# mb.net
KiCad netlist of a schematic drawn in Altium Designer
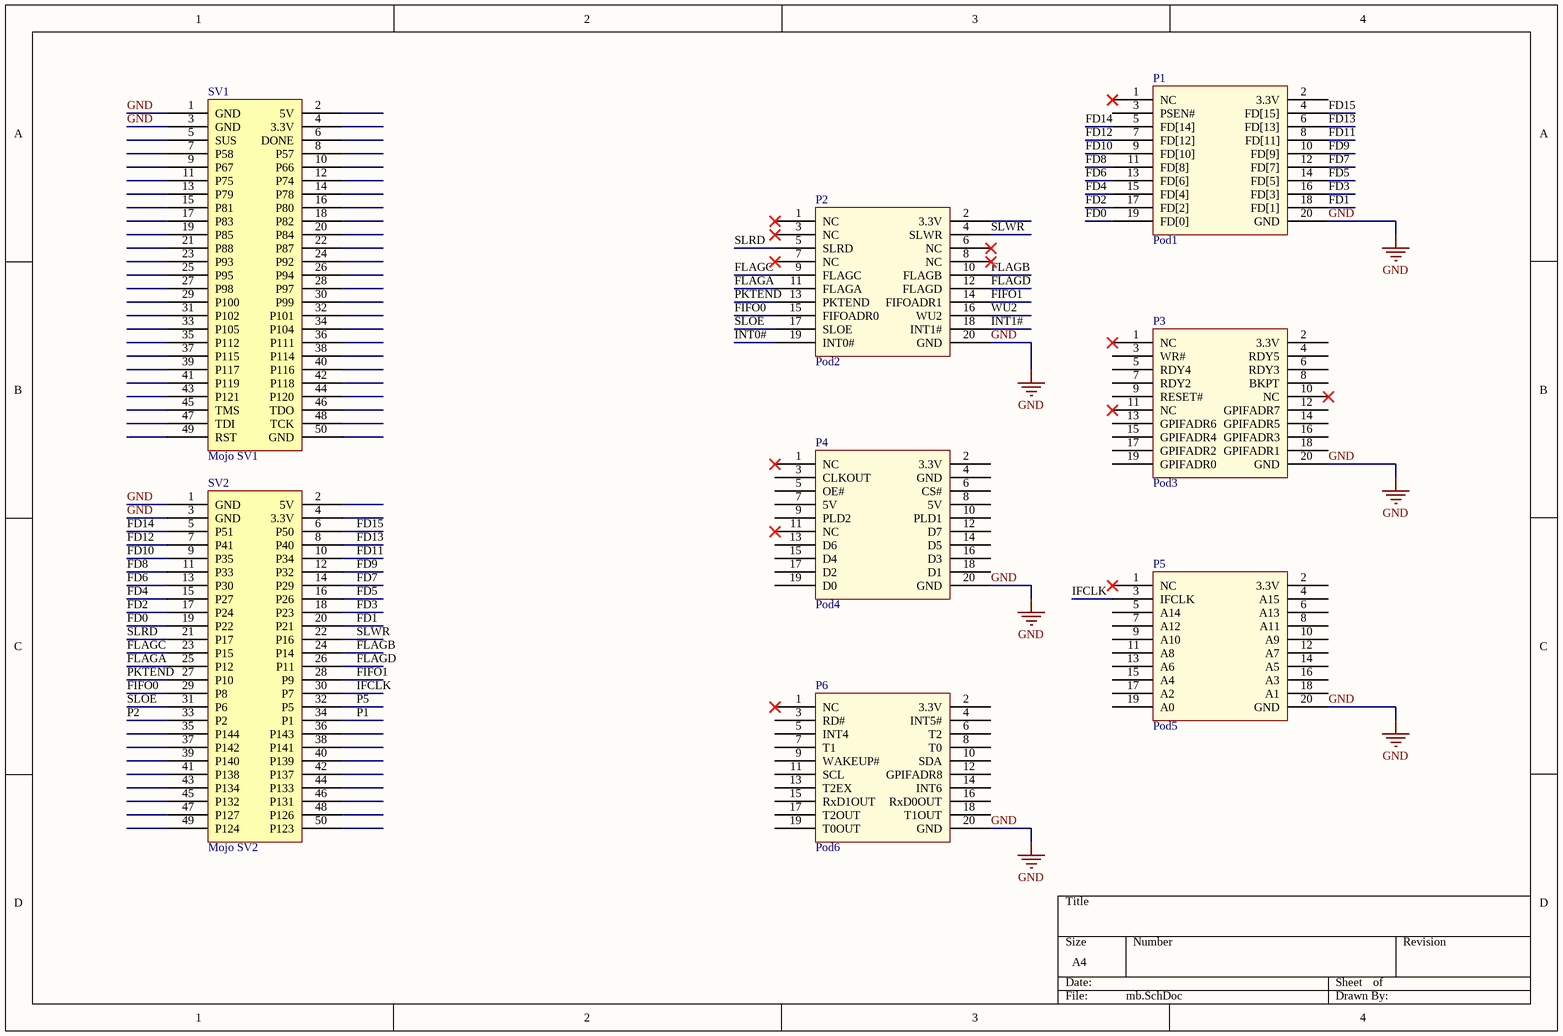
[diagram p0: mb.SchDoc]

(export (version "E")
  (design (tool "Eeschema 10.0.6"))
  (components
    (comp (ref "P1") (value "Pod1") (footprint "Pin Header 20x2") (libsource (lib "port1") (part "P*")))
    (comp (ref "P2") (value "Pod2") (footprint "Pin Header 20x2") (libsource (lib "port2") (part "Pod2")))
    (comp (ref "P3") (value "Pod3") (footprint "Pin Header 20x2") (libsource (lib "port3") (part "Pod3")))
    (comp (ref "P4") (value "Pod4") (footprint "Pin Header 20x2") (libsource (lib "port4") (part "Pod4")))
    (comp (ref "P5") (value "Pod5") (footprint "Pin Header 20x2") (libsource (lib "port5") (part "Pod5")))
    (comp (ref "P6") (value "Pod6") (footprint "Pin Header 20x2") (libsource (lib "port6") (part "Pod6")))
    (comp (ref "SV1") (value "Mojo SV1") (footprint "PH25X2") (libsource (lib "mojosv1") (part "SV1")))
    (comp (ref "SV2") (value "Mojo SV2") (footprint "PH25X2") (libsource (lib "mojosv2") (part "SV2")))
  )
  (nets
    (net (code "1") (name "/FD0") (class "Default")
      (node (ref "P1") (pin "19") (pinfunction "FD[0]_19") (pintype "passive"))
      (node (ref "SV2") (pin "19") (pinfunction "P22_19") (pintype "passive"))
    )
    (net (code "2") (name "/FD1") (class "Default")
      (node (ref "P1") (pin "18") (pinfunction "FD[1]_18") (pintype "passive"))
      (node (ref "SV2") (pin "20") (pinfunction "P21_20") (pintype "passive"))
    )
    (net (code "3") (name "/FD2") (class "Default")
      (node (ref "P1") (pin "17") (pinfunction "FD[2]_17") (pintype "passive"))
      (node (ref "SV2") (pin "17") (pinfunction "P24_17") (pintype "passive"))
    )
    (net (code "4") (name "/FD3") (class "Default")
      (node (ref "P1") (pin "16") (pinfunction "FD[3]_16") (pintype "passive"))
      (node (ref "SV2") (pin "18") (pinfunction "P23_18") (pintype "passive"))
    )
    (net (code "5") (name "/FD4") (class "Default")
      (node (ref "P1") (pin "15") (pinfunction "FD[4]_15") (pintype "passive"))
      (node (ref "SV2") (pin "15") (pinfunction "P27_15") (pintype "passive"))
    )
    (net (code "6") (name "/FD5") (class "Default")
      (node (ref "P1") (pin "14") (pinfunction "FD[5]_14") (pintype "passive"))
      (node (ref "SV2") (pin "16") (pinfunction "P26_16") (pintype "passive"))
    )
    (net (code "7") (name "/FD6") (class "Default")
      (node (ref "P1") (pin "13") (pinfunction "FD[6]_13") (pintype "passive"))
      (node (ref "SV2") (pin "13") (pinfunction "P30_13") (pintype "passive"))
    )
    (net (code "8") (name "/FD7") (class "Default")
      (node (ref "P1") (pin "12") (pinfunction "FD[7]_12") (pintype "passive"))
      (node (ref "SV2") (pin "14") (pinfunction "P29_14") (pintype "passive"))
    )
    (net (code "9") (name "/FD8") (class "Default")
      (node (ref "P1") (pin "11") (pinfunction "FD[8]_11") (pintype "passive"))
      (node (ref "SV2") (pin "11") (pinfunction "P33_11") (pintype "passive"))
    )
    (net (code "10") (name "/FD9") (class "Default")
      (node (ref "P1") (pin "10") (pinfunction "FD[9]_10") (pintype "passive"))
      (node (ref "SV2") (pin "12") (pinfunction "P32_12") (pintype "passive"))
    )
    (net (code "11") (name "/FD10") (class "Default")
      (node (ref "P1") (pin "9") (pinfunction "FD[10]_9") (pintype "passive"))
      (node (ref "SV2") (pin "9") (pinfunction "P35_9") (pintype "passive"))
    )
    (net (code "12") (name "/FD11") (class "Default")
      (node (ref "P1") (pin "8") (pinfunction "FD[11]_8") (pintype "passive"))
      (node (ref "SV2") (pin "10") (pinfunction "P34_10") (pintype "passive"))
    )
    (net (code "13") (name "/FD12") (class "Default")
      (node (ref "P1") (pin "7") (pinfunction "FD[12]_7") (pintype "passive"))
      (node (ref "SV2") (pin "7") (pinfunction "P41_7") (pintype "passive"))
    )
    (net (code "14") (name "/FD13") (class "Default")
      (node (ref "P1") (pin "6") (pinfunction "FD[13]_6") (pintype "passive"))
      (node (ref "SV2") (pin "8") (pinfunction "P40_8") (pintype "passive"))
    )
    (net (code "15") (name "/FD14") (class "Default")
      (node (ref "P1") (pin "5") (pinfunction "FD[14]_5") (pintype "passive"))
      (node (ref "SV2") (pin "5") (pinfunction "P51_5") (pintype "passive"))
    )
    (net (code "16") (name "/FD15") (class "Default")
      (node (ref "P1") (pin "4") (pinfunction "FD[15]_4") (pintype "passive"))
      (node (ref "SV2") (pin "6") (pinfunction "P50_6") (pintype "passive"))
    )
    (net (code "17") (name "/FIFO0") (class "Default")
      (node (ref "P2") (pin "15") (pinfunction "FIFOADR0_15") (pintype "passive"))
      (node (ref "SV2") (pin "29") (pinfunction "P8_29") (pintype "passive"))
    )
    (net (code "18") (name "/FIFO1") (class "Default")
      (node (ref "P2") (pin "14") (pinfunction "FIFOADR1_14") (pintype "passive"))
      (node (ref "SV2") (pin "28") (pinfunction "P9_28") (pintype "passive"))
    )
    (net (code "19") (name "/FLAGA") (class "Default")
      (node (ref "P2") (pin "11") (pinfunction "FLAGA_11") (pintype "passive"))
      (node (ref "SV2") (pin "25") (pinfunction "P12_25") (pintype "passive"))
    )
    (net (code "20") (name "/FLAGB") (class "Default")
      (node (ref "P2") (pin "10") (pinfunction "FLAGB_10") (pintype "passive"))
      (node (ref "SV2") (pin "24") (pinfunction "P14_24") (pintype "passive"))
    )
    (net (code "21") (name "/FLAGC") (class "Default")
      (node (ref "P2") (pin "9") (pinfunction "FLAGC_9") (pintype "passive"))
      (node (ref "SV2") (pin "23") (pinfunction "P15_23") (pintype "passive"))
    )
    (net (code "22") (name "/FLAGD") (class "Default")
      (node (ref "P2") (pin "12") (pinfunction "FLAGD_12") (pintype "passive"))
      (node (ref "SV2") (pin "26") (pinfunction "P11_26") (pintype "passive"))
    )
    (net (code "23") (name "/IFCLK") (class "Default")
      (node (ref "P5") (pin "3") (pinfunction "IFCLK_3") (pintype "passive"))
      (node (ref "SV2") (pin "30") (pinfunction "P7_30") (pintype "passive"))
    )
    (net (code "24") (name "/INT0#") (class "Default")
      (node (ref "P2") (pin "19") (pinfunction "INT0#_19") (pintype "passive"))
    )
    (net (code "25") (name "/INT1#") (class "Default")
      (node (ref "P2") (pin "18") (pinfunction "INT1#_18") (pintype "passive"))
    )
    (net (code "26") (name "/P1") (class "Default")
      (node (ref "SV2") (pin "34") (pinfunction "P1_34") (pintype "passive"))
    )
    (net (code "27") (name "/P2") (class "Default")
      (node (ref "SV2") (pin "33") (pinfunction "P2_33") (pintype "passive"))
    )
    (net (code "28") (name "/P5") (class "Default")
      (node (ref "SV2") (pin "32") (pinfunction "P5_32") (pintype "passive"))
    )
    (net (code "29") (name "/PKTEND") (class "Default")
      (node (ref "P2") (pin "13") (pinfunction "PKTEND_13") (pintype "passive"))
      (node (ref "SV2") (pin "27") (pinfunction "P10_27") (pintype "passive"))
    )
    (net (code "30") (name "/SLOE") (class "Default")
      (node (ref "P2") (pin "17") (pinfunction "SLOE_17") (pintype "passive"))
      (node (ref "SV2") (pin "31") (pinfunction "P6_31") (pintype "passive"))
    )
    (net (code "31") (name "/SLRD") (class "Default")
      (node (ref "P2") (pin "5") (pinfunction "SLRD_5") (pintype "passive"))
      (node (ref "SV2") (pin "21") (pinfunction "P17_21") (pintype "passive"))
    )
    (net (code "32") (name "/SLWR") (class "Default")
      (node (ref "P2") (pin "4") (pinfunction "SLWR_4") (pintype "passive"))
      (node (ref "SV2") (pin "22") (pinfunction "P16_22") (pintype "passive"))
    )
    (net (code "33") (name "/WU2") (class "Default")
      (node (ref "P2") (pin "16") (pinfunction "WU2_16") (pintype "passive"))
    )
    (net (code "34") (name "GND") (class "Default")
      (node (ref "P1") (pin "20") (pinfunction "GND_20") (pintype "passive"))
      (node (ref "P2") (pin "20") (pinfunction "GND_20") (pintype "passive"))
      (node (ref "P3") (pin "20") (pinfunction "GND_20") (pintype "passive"))
      (node (ref "P4") (pin "20") (pinfunction "GND_20") (pintype "passive"))
      (node (ref "P5") (pin "20") (pinfunction "GND_20") (pintype "passive"))
      (node (ref "P6") (pin "20") (pinfunction "GND_20") (pintype "passive"))
      (node (ref "SV1") (pin "1") (pinfunction "GND_1") (pintype "passive"))
      (node (ref "SV1") (pin "3") (pinfunction "GND_3") (pintype "passive"))
      (node (ref "SV2") (pin "1") (pinfunction "GND_1") (pintype "passive"))
      (node (ref "SV2") (pin "3") (pinfunction "GND_3") (pintype "passive"))
    )
    (net (code "35") (name "unconnected-(P1-3.3V-Pad2)") (class "Default")
      (node (ref "P1") (pin "2") (pinfunction "3.3V_2") (pintype "passive"))
    )
    (net (code "36") (name "unconnected-(P1-NC-Pad1)") (class "Default")
      (node (ref "P1") (pin "1") (pinfunction "NC_1") (pintype "passive+no_connect"))
    )
    (net (code "37") (name "unconnected-(P1-PSEN#-Pad3)") (class "Default")
      (node (ref "P1") (pin "3") (pinfunction "PSEN#_3") (pintype "passive"))
    )
    (net (code "38") (name "unconnected-(P2-3.3V-Pad2)") (class "Default")
      (node (ref "P2") (pin "2") (pinfunction "3.3V_2") (pintype "passive"))
    )
    (net (code "39") (name "unconnected-(P2-NC-Pad1)") (class "Default")
      (node (ref "P2") (pin "1") (pinfunction "NC_1") (pintype "passive+no_connect"))
    )
    (net (code "40") (name "unconnected-(P2-NC-Pad3)") (class "Default")
      (node (ref "P2") (pin "3") (pinfunction "NC_3") (pintype "passive+no_connect"))
    )
    (net (code "41") (name "unconnected-(P2-NC-Pad6)") (class "Default")
      (node (ref "P2") (pin "6") (pinfunction "NC_6") (pintype "passive+no_connect"))
    )
    (net (code "42") (name "unconnected-(P2-NC-Pad7)") (class "Default")
      (node (ref "P2") (pin "7") (pinfunction "NC_7") (pintype "passive+no_connect"))
    )
    (net (code "43") (name "unconnected-(P2-NC-Pad8)") (class "Default")
      (node (ref "P2") (pin "8") (pinfunction "NC_8") (pintype "passive+no_connect"))
    )
    (net (code "44") (name "unconnected-(P3-3.3V-Pad2)") (class "Default")
      (node (ref "P3") (pin "2") (pinfunction "3.3V_2") (pintype "passive"))
    )
    (net (code "45") (name "unconnected-(P3-BKPT-Pad8)") (class "Default")
      (node (ref "P3") (pin "8") (pinfunction "BKPT_8") (pintype "passive"))
    )
    (net (code "46") (name "unconnected-(P3-GPIFADR0-Pad19)") (class "Default")
      (node (ref "P3") (pin "19") (pinfunction "GPIFADR0_19") (pintype "passive"))
    )
    (net (code "47") (name "unconnected-(P3-GPIFADR1-Pad18)") (class "Default")
      (node (ref "P3") (pin "18") (pinfunction "GPIFADR1_18") (pintype "passive"))
    )
    (net (code "48") (name "unconnected-(P3-GPIFADR2-Pad17)") (class "Default")
      (node (ref "P3") (pin "17") (pinfunction "GPIFADR2_17") (pintype "passive"))
    )
    (net (code "49") (name "unconnected-(P3-GPIFADR3-Pad16)") (class "Default")
      (node (ref "P3") (pin "16") (pinfunction "GPIFADR3_16") (pintype "passive"))
    )
    (net (code "50") (name "unconnected-(P3-GPIFADR4-Pad15)") (class "Default")
      (node (ref "P3") (pin "15") (pinfunction "GPIFADR4_15") (pintype "passive"))
    )
    (net (code "51") (name "unconnected-(P3-GPIFADR5-Pad14)") (class "Default")
      (node (ref "P3") (pin "14") (pinfunction "GPIFADR5_14") (pintype "passive"))
    )
    (net (code "52") (name "unconnected-(P3-GPIFADR6-Pad13)") (class "Default")
      (node (ref "P3") (pin "13") (pinfunction "GPIFADR6_13") (pintype "passive"))
    )
    (net (code "53") (name "unconnected-(P3-GPIFADR7-Pad12)") (class "Default")
      (node (ref "P3") (pin "12") (pinfunction "GPIFADR7_12") (pintype "passive"))
    )
    (net (code "54") (name "unconnected-(P3-NC-Pad1)") (class "Default")
      (node (ref "P3") (pin "1") (pinfunction "NC_1") (pintype "passive+no_connect"))
    )
    (net (code "55") (name "unconnected-(P3-NC-Pad10)") (class "Default")
      (node (ref "P3") (pin "10") (pinfunction "NC_10") (pintype "passive+no_connect"))
    )
    (net (code "56") (name "unconnected-(P3-NC-Pad11)") (class "Default")
      (node (ref "P3") (pin "11") (pinfunction "NC_11") (pintype "passive+no_connect"))
    )
    (net (code "57") (name "unconnected-(P3-RDY2-Pad7)") (class "Default")
      (node (ref "P3") (pin "7") (pinfunction "RDY2_7") (pintype "passive"))
    )
    (net (code "58") (name "unconnected-(P3-RDY3-Pad6)") (class "Default")
      (node (ref "P3") (pin "6") (pinfunction "RDY3_6") (pintype "passive"))
    )
    (net (code "59") (name "unconnected-(P3-RDY4-Pad5)") (class "Default")
      (node (ref "P3") (pin "5") (pinfunction "RDY4_5") (pintype "passive"))
    )
    (net (code "60") (name "unconnected-(P3-RDY5-Pad4)") (class "Default")
      (node (ref "P3") (pin "4") (pinfunction "RDY5_4") (pintype "passive"))
    )
    (net (code "61") (name "unconnected-(P3-RESET#-Pad9)") (class "Default")
      (node (ref "P3") (pin "9") (pinfunction "RESET#_9") (pintype "passive"))
    )
    (net (code "62") (name "unconnected-(P3-WR#-Pad3)") (class "Default")
      (node (ref "P3") (pin "3") (pinfunction "WR#_3") (pintype "passive"))
    )
    (net (code "63") (name "unconnected-(P4-3.3V-Pad2)") (class "Default")
      (node (ref "P4") (pin "2") (pinfunction "3.3V_2") (pintype "passive"))
    )
    (net (code "64") (name "unconnected-(P4-5V-Pad7)") (class "Default")
      (node (ref "P4") (pin "7") (pinfunction "5V_7") (pintype "passive"))
    )
    (net (code "65") (name "unconnected-(P4-5V-Pad8)") (class "Default")
      (node (ref "P4") (pin "8") (pinfunction "5V_8") (pintype "passive"))
    )
    (net (code "66") (name "unconnected-(P4-CLKOUT-Pad3)") (class "Default")
      (node (ref "P4") (pin "3") (pinfunction "CLKOUT_3") (pintype "passive"))
    )
    (net (code "67") (name "unconnected-(P4-CS#-Pad6)") (class "Default")
      (node (ref "P4") (pin "6") (pinfunction "CS#_6") (pintype "passive"))
    )
    (net (code "68") (name "unconnected-(P4-D0-Pad19)") (class "Default")
      (node (ref "P4") (pin "19") (pinfunction "D0_19") (pintype "passive"))
    )
    (net (code "69") (name "unconnected-(P4-D1-Pad18)") (class "Default")
      (node (ref "P4") (pin "18") (pinfunction "D1_18") (pintype "passive"))
    )
    (net (code "70") (name "unconnected-(P4-D2-Pad17)") (class "Default")
      (node (ref "P4") (pin "17") (pinfunction "D2_17") (pintype "passive"))
    )
    (net (code "71") (name "unconnected-(P4-D3-Pad16)") (class "Default")
      (node (ref "P4") (pin "16") (pinfunction "D3_16") (pintype "passive"))
    )
    (net (code "72") (name "unconnected-(P4-D4-Pad15)") (class "Default")
      (node (ref "P4") (pin "15") (pinfunction "D4_15") (pintype "passive"))
    )
    (net (code "73") (name "unconnected-(P4-D5-Pad14)") (class "Default")
      (node (ref "P4") (pin "14") (pinfunction "D5_14") (pintype "passive"))
    )
    (net (code "74") (name "unconnected-(P4-D6-Pad13)") (class "Default")
      (node (ref "P4") (pin "13") (pinfunction "D6_13") (pintype "passive"))
    )
    (net (code "75") (name "unconnected-(P4-D7-Pad12)") (class "Default")
      (node (ref "P4") (pin "12") (pinfunction "D7_12") (pintype "passive"))
    )
    (net (code "76") (name "unconnected-(P4-GND-Pad4)") (class "Default")
      (node (ref "P4") (pin "4") (pinfunction "GND_4") (pintype "passive"))
    )
    (net (code "77") (name "unconnected-(P4-NC-Pad1)") (class "Default")
      (node (ref "P4") (pin "1") (pinfunction "NC_1") (pintype "passive+no_connect"))
    )
    (net (code "78") (name "unconnected-(P4-NC-Pad11)") (class "Default")
      (node (ref "P4") (pin "11") (pinfunction "NC_11") (pintype "passive+no_connect"))
    )
    (net (code "79") (name "unconnected-(P4-OE#-Pad5)") (class "Default")
      (node (ref "P4") (pin "5") (pinfunction "OE#_5") (pintype "passive"))
    )
    (net (code "80") (name "unconnected-(P4-PLD1-Pad10)") (class "Default")
      (node (ref "P4") (pin "10") (pinfunction "PLD1_10") (pintype "passive"))
    )
    (net (code "81") (name "unconnected-(P4-PLD2-Pad9)") (class "Default")
      (node (ref "P4") (pin "9") (pinfunction "PLD2_9") (pintype "passive"))
    )
    (net (code "82") (name "unconnected-(P5-3.3V-Pad2)") (class "Default")
      (node (ref "P5") (pin "2") (pinfunction "3.3V_2") (pintype "passive"))
    )
    (net (code "83") (name "unconnected-(P5-A0-Pad19)") (class "Default")
      (node (ref "P5") (pin "19") (pinfunction "A0_19") (pintype "passive"))
    )
    (net (code "84") (name "unconnected-(P5-A1-Pad18)") (class "Default")
      (node (ref "P5") (pin "18") (pinfunction "A1_18") (pintype "passive"))
    )
    (net (code "85") (name "unconnected-(P5-A2-Pad17)") (class "Default")
      (node (ref "P5") (pin "17") (pinfunction "A2_17") (pintype "passive"))
    )
    (net (code "86") (name "unconnected-(P5-A3-Pad16)") (class "Default")
      (node (ref "P5") (pin "16") (pinfunction "A3_16") (pintype "passive"))
    )
    (net (code "87") (name "unconnected-(P5-A4-Pad15)") (class "Default")
      (node (ref "P5") (pin "15") (pinfunction "A4_15") (pintype "passive"))
    )
    (net (code "88") (name "unconnected-(P5-A5-Pad14)") (class "Default")
      (node (ref "P5") (pin "14") (pinfunction "A5_14") (pintype "passive"))
    )
    (net (code "89") (name "unconnected-(P5-A6-Pad13)") (class "Default")
      (node (ref "P5") (pin "13") (pinfunction "A6_13") (pintype "passive"))
    )
    (net (code "90") (name "unconnected-(P5-A7-Pad12)") (class "Default")
      (node (ref "P5") (pin "12") (pinfunction "A7_12") (pintype "passive"))
    )
    (net (code "91") (name "unconnected-(P5-A8-Pad11)") (class "Default")
      (node (ref "P5") (pin "11") (pinfunction "A8_11") (pintype "passive"))
    )
    (net (code "92") (name "unconnected-(P5-A9-Pad10)") (class "Default")
      (node (ref "P5") (pin "10") (pinfunction "A9_10") (pintype "passive"))
    )
    (net (code "93") (name "unconnected-(P5-A10-Pad9)") (class "Default")
      (node (ref "P5") (pin "9") (pinfunction "A10_9") (pintype "passive"))
    )
    (net (code "94") (name "unconnected-(P5-A11-Pad8)") (class "Default")
      (node (ref "P5") (pin "8") (pinfunction "A11_8") (pintype "passive"))
    )
    (net (code "95") (name "unconnected-(P5-A12-Pad7)") (class "Default")
      (node (ref "P5") (pin "7") (pinfunction "A12_7") (pintype "passive"))
    )
    (net (code "96") (name "unconnected-(P5-A13-Pad6)") (class "Default")
      (node (ref "P5") (pin "6") (pinfunction "A13_6") (pintype "passive"))
    )
    (net (code "97") (name "unconnected-(P5-A14-Pad5)") (class "Default")
      (node (ref "P5") (pin "5") (pinfunction "A14_5") (pintype "passive"))
    )
    (net (code "98") (name "unconnected-(P5-A15-Pad4)") (class "Default")
      (node (ref "P5") (pin "4") (pinfunction "A15_4") (pintype "passive"))
    )
    (net (code "99") (name "unconnected-(P5-NC-Pad1)") (class "Default")
      (node (ref "P5") (pin "1") (pinfunction "NC_1") (pintype "passive+no_connect"))
    )
    (net (code "100") (name "unconnected-(P6-3.3V-Pad2)") (class "Default")
      (node (ref "P6") (pin "2") (pinfunction "3.3V_2") (pintype "passive"))
    )
    (net (code "101") (name "unconnected-(P6-GPIFADR8-Pad12)") (class "Default")
      (node (ref "P6") (pin "12") (pinfunction "GPIFADR8_12") (pintype "passive"))
    )
    (net (code "102") (name "unconnected-(P6-INT4-Pad5)") (class "Default")
      (node (ref "P6") (pin "5") (pinfunction "INT4_5") (pintype "passive"))
    )
    (net (code "103") (name "unconnected-(P6-INT5#-Pad4)") (class "Default")
      (node (ref "P6") (pin "4") (pinfunction "INT5#_4") (pintype "passive"))
    )
    (net (code "104") (name "unconnected-(P6-INT6-Pad14)") (class "Default")
      (node (ref "P6") (pin "14") (pinfunction "INT6_14") (pintype "passive"))
    )
    (net (code "105") (name "unconnected-(P6-NC-Pad1)") (class "Default")
      (node (ref "P6") (pin "1") (pinfunction "NC_1") (pintype "passive+no_connect"))
    )
    (net (code "106") (name "unconnected-(P6-RD#-Pad3)") (class "Default")
      (node (ref "P6") (pin "3") (pinfunction "RD#_3") (pintype "passive"))
    )
    (net (code "107") (name "unconnected-(P6-RxD0OUT-Pad16)") (class "Default")
      (node (ref "P6") (pin "16") (pinfunction "RxD0OUT_16") (pintype "passive"))
    )
    (net (code "108") (name "unconnected-(P6-RxD1OUT-Pad15)") (class "Default")
      (node (ref "P6") (pin "15") (pinfunction "RxD1OUT_15") (pintype "passive"))
    )
    (net (code "109") (name "unconnected-(P6-SCL-Pad11)") (class "Default")
      (node (ref "P6") (pin "11") (pinfunction "SCL_11") (pintype "passive"))
    )
    (net (code "110") (name "unconnected-(P6-SDA-Pad10)") (class "Default")
      (node (ref "P6") (pin "10") (pinfunction "SDA_10") (pintype "passive"))
    )
    (net (code "111") (name "unconnected-(P6-T0-Pad8)") (class "Default")
      (node (ref "P6") (pin "8") (pinfunction "T0_8") (pintype "passive"))
    )
    (net (code "112") (name "unconnected-(P6-T0OUT-Pad19)") (class "Default")
      (node (ref "P6") (pin "19") (pinfunction "T0OUT_19") (pintype "passive"))
    )
    (net (code "113") (name "unconnected-(P6-T1-Pad7)") (class "Default")
      (node (ref "P6") (pin "7") (pinfunction "T1_7") (pintype "passive"))
    )
    (net (code "114") (name "unconnected-(P6-T1OUT-Pad18)") (class "Default")
      (node (ref "P6") (pin "18") (pinfunction "T1OUT_18") (pintype "passive"))
    )
    (net (code "115") (name "unconnected-(P6-T2-Pad6)") (class "Default")
      (node (ref "P6") (pin "6") (pinfunction "T2_6") (pintype "passive"))
    )
    (net (code "116") (name "unconnected-(P6-T2EX-Pad13)") (class "Default")
      (node (ref "P6") (pin "13") (pinfunction "T2EX_13") (pintype "passive"))
    )
    (net (code "117") (name "unconnected-(P6-T2OUT-Pad17)") (class "Default")
      (node (ref "P6") (pin "17") (pinfunction "T2OUT_17") (pintype "passive"))
    )
    (net (code "118") (name "unconnected-(P6-WAKEUP#-Pad9)") (class "Default")
      (node (ref "P6") (pin "9") (pinfunction "WAKEUP#_9") (pintype "passive"))
    )
    (net (code "119") (name "unconnected-(SV1-3.3V-Pad4)") (class "Default")
      (node (ref "SV1") (pin "4") (pinfunction "3.3V_4") (pintype "passive"))
    )
    (net (code "120") (name "unconnected-(SV1-5V-Pad2)") (class "Default")
      (node (ref "SV1") (pin "2") (pinfunction "5V_2") (pintype "passive"))
    )
    (net (code "121") (name "unconnected-(SV1-DONE-Pad6)") (class "Default")
      (node (ref "SV1") (pin "6") (pinfunction "DONE_6") (pintype "passive"))
    )
    (net (code "122") (name "unconnected-(SV1-GND-Pad50)") (class "Default")
      (node (ref "SV1") (pin "50") (pinfunction "GND_50") (pintype "passive"))
    )
    (net (code "123") (name "unconnected-(SV1-P57-Pad8)") (class "Default")
      (node (ref "SV1") (pin "8") (pinfunction "P57_8") (pintype "passive"))
    )
    (net (code "124") (name "unconnected-(SV1-P58-Pad7)") (class "Default")
      (node (ref "SV1") (pin "7") (pinfunction "P58_7") (pintype "passive"))
    )
    (net (code "125") (name "unconnected-(SV1-P66-Pad10)") (class "Default")
      (node (ref "SV1") (pin "10") (pinfunction "P66_10") (pintype "passive"))
    )
    (net (code "126") (name "unconnected-(SV1-P67-Pad9)") (class "Default")
      (node (ref "SV1") (pin "9") (pinfunction "P67_9") (pintype "passive"))
    )
    (net (code "127") (name "unconnected-(SV1-P74-Pad12)") (class "Default")
      (node (ref "SV1") (pin "12") (pinfunction "P74_12") (pintype "passive"))
    )
    (net (code "128") (name "unconnected-(SV1-P75-Pad11)") (class "Default")
      (node (ref "SV1") (pin "11") (pinfunction "P75_11") (pintype "passive"))
    )
    (net (code "129") (name "unconnected-(SV1-P78-Pad14)") (class "Default")
      (node (ref "SV1") (pin "14") (pinfunction "P78_14") (pintype "passive"))
    )
    (net (code "130") (name "unconnected-(SV1-P79-Pad13)") (class "Default")
      (node (ref "SV1") (pin "13") (pinfunction "P79_13") (pintype "passive"))
    )
    (net (code "131") (name "unconnected-(SV1-P80-Pad16)") (class "Default")
      (node (ref "SV1") (pin "16") (pinfunction "P80_16") (pintype "passive"))
    )
    (net (code "132") (name "unconnected-(SV1-P81-Pad15)") (class "Default")
      (node (ref "SV1") (pin "15") (pinfunction "P81_15") (pintype "passive"))
    )
    (net (code "133") (name "unconnected-(SV1-P82-Pad18)") (class "Default")
      (node (ref "SV1") (pin "18") (pinfunction "P82_18") (pintype "passive"))
    )
    (net (code "134") (name "unconnected-(SV1-P83-Pad17)") (class "Default")
      (node (ref "SV1") (pin "17") (pinfunction "P83_17") (pintype "passive"))
    )
    (net (code "135") (name "unconnected-(SV1-P84-Pad20)") (class "Default")
      (node (ref "SV1") (pin "20") (pinfunction "P84_20") (pintype "passive"))
    )
    (net (code "136") (name "unconnected-(SV1-P85-Pad19)") (class "Default")
      (node (ref "SV1") (pin "19") (pinfunction "P85_19") (pintype "passive"))
    )
    (net (code "137") (name "unconnected-(SV1-P87-Pad22)") (class "Default")
      (node (ref "SV1") (pin "22") (pinfunction "P87_22") (pintype "passive"))
    )
    (net (code "138") (name "unconnected-(SV1-P88-Pad21)") (class "Default")
      (node (ref "SV1") (pin "21") (pinfunction "P88_21") (pintype "passive"))
    )
    (net (code "139") (name "unconnected-(SV1-P92-Pad24)") (class "Default")
      (node (ref "SV1") (pin "24") (pinfunction "P92_24") (pintype "passive"))
    )
    (net (code "140") (name "unconnected-(SV1-P93-Pad23)") (class "Default")
      (node (ref "SV1") (pin "23") (pinfunction "P93_23") (pintype "passive"))
    )
    (net (code "141") (name "unconnected-(SV1-P94-Pad26)") (class "Default")
      (node (ref "SV1") (pin "26") (pinfunction "P94_26") (pintype "passive"))
    )
    (net (code "142") (name "unconnected-(SV1-P95-Pad25)") (class "Default")
      (node (ref "SV1") (pin "25") (pinfunction "P95_25") (pintype "passive"))
    )
    (net (code "143") (name "unconnected-(SV1-P97-Pad28)") (class "Default")
      (node (ref "SV1") (pin "28") (pinfunction "P97_28") (pintype "passive"))
    )
    (net (code "144") (name "unconnected-(SV1-P98-Pad27)") (class "Default")
      (node (ref "SV1") (pin "27") (pinfunction "P98_27") (pintype "passive"))
    )
    (net (code "145") (name "unconnected-(SV1-P99-Pad30)") (class "Default")
      (node (ref "SV1") (pin "30") (pinfunction "P99_30") (pintype "passive"))
    )
    (net (code "146") (name "unconnected-(SV1-P100-Pad29)") (class "Default")
      (node (ref "SV1") (pin "29") (pinfunction "P100_29") (pintype "passive"))
    )
    (net (code "147") (name "unconnected-(SV1-P101-Pad32)") (class "Default")
      (node (ref "SV1") (pin "32") (pinfunction "P101_32") (pintype "passive"))
    )
    (net (code "148") (name "unconnected-(SV1-P102-Pad31)") (class "Default")
      (node (ref "SV1") (pin "31") (pinfunction "P102_31") (pintype "passive"))
    )
    (net (code "149") (name "unconnected-(SV1-P104-Pad34)") (class "Default")
      (node (ref "SV1") (pin "34") (pinfunction "P104_34") (pintype "passive"))
    )
    (net (code "150") (name "unconnected-(SV1-P105-Pad33)") (class "Default")
      (node (ref "SV1") (pin "33") (pinfunction "P105_33") (pintype "passive"))
    )
    (net (code "151") (name "unconnected-(SV1-P111-Pad36)") (class "Default")
      (node (ref "SV1") (pin "36") (pinfunction "P111_36") (pintype "passive"))
    )
    (net (code "152") (name "unconnected-(SV1-P112-Pad35)") (class "Default")
      (node (ref "SV1") (pin "35") (pinfunction "P112_35") (pintype "passive"))
    )
    (net (code "153") (name "unconnected-(SV1-P114-Pad38)") (class "Default")
      (node (ref "SV1") (pin "38") (pinfunction "P114_38") (pintype "passive"))
    )
    (net (code "154") (name "unconnected-(SV1-P115-Pad37)") (class "Default")
      (node (ref "SV1") (pin "37") (pinfunction "P115_37") (pintype "passive"))
    )
    (net (code "155") (name "unconnected-(SV1-P116-Pad40)") (class "Default")
      (node (ref "SV1") (pin "40") (pinfunction "P116_40") (pintype "passive"))
    )
    (net (code "156") (name "unconnected-(SV1-P117-Pad39)") (class "Default")
      (node (ref "SV1") (pin "39") (pinfunction "P117_39") (pintype "passive"))
    )
    (net (code "157") (name "unconnected-(SV1-P118-Pad42)") (class "Default")
      (node (ref "SV1") (pin "42") (pinfunction "P118_42") (pintype "passive"))
    )
    (net (code "158") (name "unconnected-(SV1-P119-Pad41)") (class "Default")
      (node (ref "SV1") (pin "41") (pinfunction "P119_41") (pintype "passive"))
    )
    (net (code "159") (name "unconnected-(SV1-P120-Pad44)") (class "Default")
      (node (ref "SV1") (pin "44") (pinfunction "P120_44") (pintype "passive"))
    )
    (net (code "160") (name "unconnected-(SV1-P121-Pad43)") (class "Default")
      (node (ref "SV1") (pin "43") (pinfunction "P121_43") (pintype "passive"))
    )
    (net (code "161") (name "unconnected-(SV1-RST-Pad49)") (class "Default")
      (node (ref "SV1") (pin "49") (pinfunction "RST_49") (pintype "passive"))
    )
    (net (code "162") (name "unconnected-(SV1-SUS-Pad5)") (class "Default")
      (node (ref "SV1") (pin "5") (pinfunction "SUS_5") (pintype "passive"))
    )
    (net (code "163") (name "unconnected-(SV1-TCK-Pad48)") (class "Default")
      (node (ref "SV1") (pin "48") (pinfunction "TCK_48") (pintype "passive"))
    )
    (net (code "164") (name "unconnected-(SV1-TDI-Pad47)") (class "Default")
      (node (ref "SV1") (pin "47") (pinfunction "TDI_47") (pintype "passive"))
    )
    (net (code "165") (name "unconnected-(SV1-TDO-Pad46)") (class "Default")
      (node (ref "SV1") (pin "46") (pinfunction "TDO_46") (pintype "passive"))
    )
    (net (code "166") (name "unconnected-(SV1-TMS-Pad45)") (class "Default")
      (node (ref "SV1") (pin "45") (pinfunction "TMS_45") (pintype "passive"))
    )
    (net (code "167") (name "unconnected-(SV2-3.3V-Pad4)") (class "Default")
      (node (ref "SV2") (pin "4") (pinfunction "3.3V_4") (pintype "passive"))
    )
    (net (code "168") (name "unconnected-(SV2-5V-Pad2)") (class "Default")
      (node (ref "SV2") (pin "2") (pinfunction "5V_2") (pintype "passive"))
    )
    (net (code "169") (name "unconnected-(SV2-P123-Pad50)") (class "Default")
      (node (ref "SV2") (pin "50") (pinfunction "P123_50") (pintype "passive"))
    )
    (net (code "170") (name "unconnected-(SV2-P124-Pad49)") (class "Default")
      (node (ref "SV2") (pin "49") (pinfunction "P124_49") (pintype "passive"))
    )
    (net (code "171") (name "unconnected-(SV2-P126-Pad48)") (class "Default")
      (node (ref "SV2") (pin "48") (pinfunction "P126_48") (pintype "passive"))
    )
    (net (code "172") (name "unconnected-(SV2-P127-Pad47)") (class "Default")
      (node (ref "SV2") (pin "47") (pinfunction "P127_47") (pintype "passive"))
    )
    (net (code "173") (name "unconnected-(SV2-P131-Pad46)") (class "Default")
      (node (ref "SV2") (pin "46") (pinfunction "P131_46") (pintype "passive"))
    )
    (net (code "174") (name "unconnected-(SV2-P132-Pad45)") (class "Default")
      (node (ref "SV2") (pin "45") (pinfunction "P132_45") (pintype "passive"))
    )
    (net (code "175") (name "unconnected-(SV2-P133-Pad44)") (class "Default")
      (node (ref "SV2") (pin "44") (pinfunction "P133_44") (pintype "passive"))
    )
    (net (code "176") (name "unconnected-(SV2-P134-Pad43)") (class "Default")
      (node (ref "SV2") (pin "43") (pinfunction "P134_43") (pintype "passive"))
    )
    (net (code "177") (name "unconnected-(SV2-P137-Pad42)") (class "Default")
      (node (ref "SV2") (pin "42") (pinfunction "P137_42") (pintype "passive"))
    )
    (net (code "178") (name "unconnected-(SV2-P138-Pad41)") (class "Default")
      (node (ref "SV2") (pin "41") (pinfunction "P138_41") (pintype "passive"))
    )
    (net (code "179") (name "unconnected-(SV2-P139-Pad40)") (class "Default")
      (node (ref "SV2") (pin "40") (pinfunction "P139_40") (pintype "passive"))
    )
    (net (code "180") (name "unconnected-(SV2-P140-Pad39)") (class "Default")
      (node (ref "SV2") (pin "39") (pinfunction "P140_39") (pintype "passive"))
    )
    (net (code "181") (name "unconnected-(SV2-P141-Pad38)") (class "Default")
      (node (ref "SV2") (pin "38") (pinfunction "P141_38") (pintype "passive"))
    )
    (net (code "182") (name "unconnected-(SV2-P142-Pad37)") (class "Default")
      (node (ref "SV2") (pin "37") (pinfunction "P142_37") (pintype "passive"))
    )
    (net (code "183") (name "unconnected-(SV2-P143-Pad36)") (class "Default")
      (node (ref "SV2") (pin "36") (pinfunction "P143_36") (pintype "passive"))
    )
    (net (code "184") (name "unconnected-(SV2-P144-Pad35)") (class "Default")
      (node (ref "SV2") (pin "35") (pinfunction "P144_35") (pintype "passive"))
    )
  )
)
